# connectors.net
KiCad netlist of a schematic drawn in Altium Designer
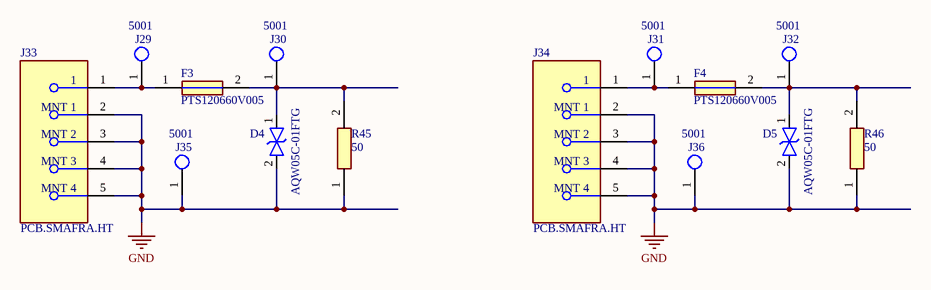
[diagram p0: connectors.SchDoc]

(export (version "E")
  (design (tool "Eeschema 10.0.6"))
  (components
    (comp (ref "D4")
      (value "AQW05C-01FTG")
      (footprint "SOD2613X100N")
      (description "TVS Diode (Bi-directional)")
      (fields (field (name "MOUSER PART NUMBER") "576-AQW05C-01FTG"))
      (libsource (lib "za_koncar") (part "AQW05C-01FTG"))
    )
    (comp (ref "D5")
      (value "AQW05C-01FTG")
      (footprint "SOD2613X100N")
      (description "TVS Diode (Bi-directional)")
      (fields (field (name "MOUSER PART NUMBER") "576-AQW05C-01FTG"))
      (libsource (lib "za_koncar") (part "AQW05C-01FTG"))
    )
    (comp (ref "F3")
      (value "PTS120660V005")
      (footprint "FUSC3216X90N")
      (description "Fuse")
      (fields (field (name "MOUSER PART NUMBER") "504-PTS120660V005"))
      (libsource (lib "za_koncar") (part "PTS120660V005"))
    )
    (comp (ref "F4")
      (value "PTS120660V005")
      (footprint "FUSC3216X90N")
      (description "Fuse")
      (fields (field (name "MOUSER PART NUMBER") "504-PTS120660V005"))
      (libsource (lib "za_koncar") (part "PTS120660V005"))
    )
    (comp (ref "J29")
      (value "5001")
      (footprint "FP-5001-MFG")
      (description "PC TEST POINT MINIATURE BLACK")
      (libsource (lib "za_koncar") (part "CMP-2000-05181-2"))
    )
    (comp (ref "J30")
      (value "5001")
      (footprint "FP-5001-MFG")
      (description "PC TEST POINT MINIATURE BLACK")
      (libsource (lib "za_koncar") (part "CMP-2000-05181-2"))
    )
    (comp (ref "J31")
      (value "5001")
      (footprint "FP-5001-MFG")
      (description "PC TEST POINT MINIATURE BLACK")
      (libsource (lib "za_koncar") (part "CMP-2000-05181-2"))
    )
    (comp (ref "J32")
      (value "5001")
      (footprint "FP-5001-MFG")
      (description "PC TEST POINT MINIATURE BLACK")
      (libsource (lib "za_koncar") (part "CMP-2000-05181-2"))
    )
    (comp (ref "J33")
      (value "PCB.SMAFRA.HT")
      (footprint "FP-PCB_SMAFRA_HT-MFG")
      (description "CONN SMA JACK R/A 50OHM PCB")
      (libsource (lib "za_koncar") (part "CMP-111093-000003-1"))
    )
    (comp (ref "J34")
      (value "PCB.SMAFRA.HT")
      (footprint "FP-PCB_SMAFRA_HT-MFG")
      (description "CONN SMA JACK R/A 50OHM PCB")
      (libsource (lib "za_koncar") (part "CMP-111093-000003-1"))
    )
    (comp (ref "J35")
      (value "5001")
      (footprint "FP-5001-MFG")
      (description "PC TEST POINT MINIATURE BLACK")
      (libsource (lib "za_koncar") (part "CMP-2000-05181-2"))
    )
    (comp (ref "J36")
      (value "5001")
      (footprint "FP-5001-MFG")
      (description "PC TEST POINT MINIATURE BLACK")
      (libsource (lib "za_koncar") (part "CMP-2000-05181-2"))
    )
    (comp (ref "R45")
      (value "50")
      (footprint "RESC6332X65N")
      (description "Resistor")
      (fields (field (name "MANUFACTURER_PART_NUMBER") "RNCL2512FT50R0"))
      (libsource (lib "za_koncar") (part "RNCL2512FT50R0"))
    )
    (comp (ref "R46")
      (value "50")
      (footprint "RESC6332X65N")
      (description "Resistor")
      (fields (field (name "MANUFACTURER_PART_NUMBER") "RNCL2512FT50R0"))
      (libsource (lib "za_koncar") (part "RNCL2512FT50R0"))
    )
  )
  (nets
    (net (code "1") (name "GND") (class "Default")
      (node (ref "D4") (pin "2") (pinfunction "2_2") (pintype "passive"))
      (node (ref "D5") (pin "2") (pinfunction "2_2") (pintype "passive"))
      (node (ref "J33") (pin "2") (pinfunction "MNT_1_2") (pintype "passive"))
      (node (ref "J33") (pin "3") (pinfunction "MNT_2_3") (pintype "passive"))
      (node (ref "J33") (pin "4") (pinfunction "MNT_3_4") (pintype "passive"))
      (node (ref "J33") (pin "5") (pinfunction "MNT_4_5") (pintype "passive"))
      (node (ref "J34") (pin "2") (pinfunction "MNT_1_2") (pintype "passive"))
      (node (ref "J34") (pin "3") (pinfunction "MNT_2_3") (pintype "passive"))
      (node (ref "J34") (pin "4") (pinfunction "MNT_3_4") (pintype "passive"))
      (node (ref "J34") (pin "5") (pinfunction "MNT_4_5") (pintype "passive"))
      (node (ref "J35") (pin "1") (pinfunction "1_1") (pintype "passive"))
      (node (ref "J36") (pin "1") (pinfunction "1_1") (pintype "passive"))
      (node (ref "R45") (pin "1") (pinfunction "1_1") (pintype "passive"))
      (node (ref "R46") (pin "1") (pinfunction "1_1") (pintype "passive"))
    )
    (net (code "2") (name "Net-(D4-Pad1)") (class "Default")
      (node (ref "D4") (pin "1") (pinfunction "1_1") (pintype "passive"))
      (node (ref "F3") (pin "2") (pinfunction "2_2") (pintype "passive"))
      (node (ref "J30") (pin "1") (pinfunction "1_1") (pintype "passive"))
      (node (ref "R45") (pin "2") (pinfunction "2_2") (pintype "passive"))
    )
    (net (code "3") (name "Net-(D5-Pad1)") (class "Default")
      (node (ref "D5") (pin "1") (pinfunction "1_1") (pintype "passive"))
      (node (ref "F4") (pin "2") (pinfunction "2_2") (pintype "passive"))
      (node (ref "J32") (pin "1") (pinfunction "1_1") (pintype "passive"))
      (node (ref "R46") (pin "2") (pinfunction "2_2") (pintype "passive"))
    )
    (net (code "4") (name "Net-(F3-Pad1)") (class "Default")
      (node (ref "F3") (pin "1") (pinfunction "1_1") (pintype "passive"))
      (node (ref "J29") (pin "1") (pinfunction "1_1") (pintype "passive"))
      (node (ref "J33") (pin "1") (pinfunction "1_1") (pintype "passive"))
    )
    (net (code "5") (name "Net-(F4-Pad1)") (class "Default")
      (node (ref "F4") (pin "1") (pinfunction "1_1") (pintype "passive"))
      (node (ref "J31") (pin "1") (pinfunction "1_1") (pintype "passive"))
      (node (ref "J34") (pin "1") (pinfunction "1_1") (pintype "passive"))
    )
  )
)
